# RS485.net
KiCad netlist of a schematic drawn in Altium Designer
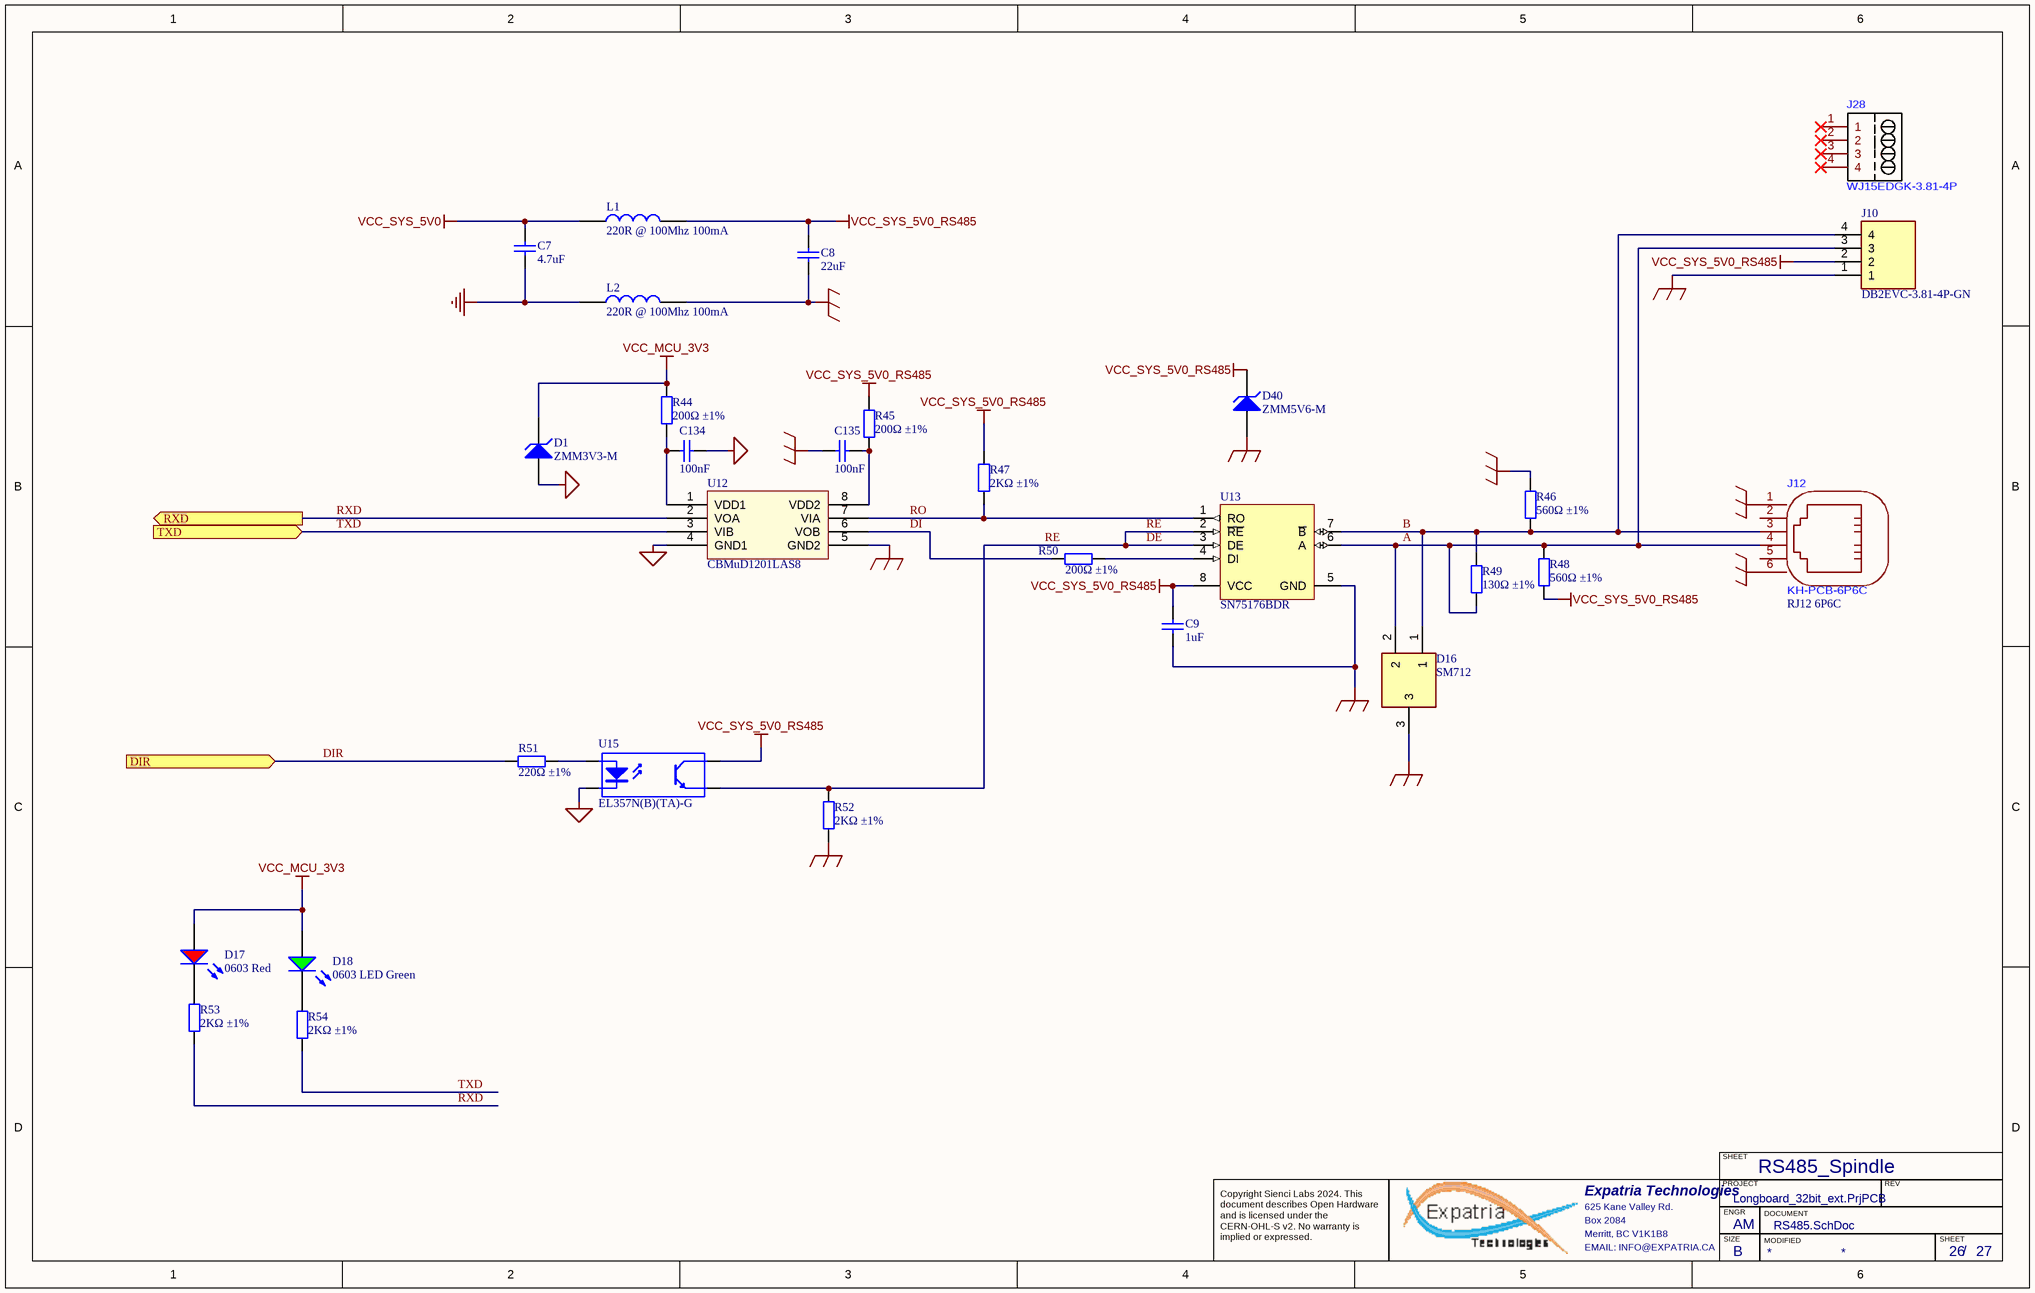
[diagram p0: RS485.SchDoc]

(export (version "E")
  (design (tool "Eeschema 10.0.6"))
  (components
    (comp (ref "C7")
      (value "4.7uF")
      (footprint "0805_C")
      (description "Chip capacitors")
      (fields
        (field (name "MANUFACTURER") "Samsung Electro-Mechanics")
        (field (name "MANUFACTURER PART NUMBER") "CL21A475KAQNNNE")
      )
      (libsource (lib "Cap") (part "0805 4.7uF (475) 10% 25V"))
    )
    (comp (ref "C8")
      (value "22uF")
      (footprint "0805_C")
      (description "25V 22uF X5R ±20% 0805 Multilayer Ceramic Capacitors MLCC - SMD/SMT ROHS")
      (fields (field (name "MANUFACTURER") "Samsung Electro-Mechanics") (field (name "TOLERANCE") "20%"))
      (libsource (lib "Sienci_Labs") (part "0805 22uF (226) 20% 25V"))
    )
    (comp (ref "C9")
      (value "1uF")
      (footprint "0603_C")
      (description "Chip capacitors")
      (fields
        (field (name "MANUFACTURER") "Samsung Electro-Mechanics")
        (field (name "MANUFACTURER PART NUMBER") "CL10A105KB8NNNC")
      )
      (libsource (lib "Cap") (part "0603 1uF (105) 10% 50V"))
    )
    (comp (ref "C134")
      (value "100nF")
      (footprint "0402_C")
      (description "16V 100nF X7R ±10% 0402 Multilayer Ceramic Capacitors MLCC - SMD/SMT ROHS")
      (fields (field (name "MANUFACTURER") "Samsung Electro-Mechanics") (field (name "TOLERANCE") "10%"))
      (libsource (lib "Sienci_Labs") (part "0402 100nF (104) 10% 16V"))
    )
    (comp (ref "C135")
      (value "100nF")
      (footprint "0402_C")
      (description "16V 100nF X7R ±10% 0402 Multilayer Ceramic Capacitors MLCC - SMD/SMT ROHS")
      (fields (field (name "MANUFACTURER") "Samsung Electro-Mechanics") (field (name "TOLERANCE") "10%"))
      (libsource (lib "Sienci_Labs") (part "0402 100nF (104) 10% 16V"))
    )
    (comp (ref "D1")
      (value "ZMM3V3-M")
      (footprint "LL-34")
      (description "Single 3.1V~3.5V 500mW 3.3V LL-34 Zener Diodes ROHS")
      (fields (field (name "MANUFACTURER") "ST(Semtech)"))
      (libsource (lib "Sienci_Labs") (part "LL-34 ZMM3V3-M"))
    )
    (comp (ref "D16")
      (value "SM712")
      (footprint "SOT95P230X117-3N")
      (description "Bidirectional 12V (Max), 7V (Max) 7.5V / 13.3V 10V / 20V 12A(8/20us) SOT-23-3 TVS RoHS")
      (fields (field (name "MANUFACTURER") "DOWO"))
      (libsource (lib "Sienci_Labs") (part "CDSOT23-SM712"))
    )
    (comp (ref "D17")
      (value "0603 Red")
      (footprint "0603_LED_S1")
      (description "-40℃~+85℃ Red 0603 Light Emitting Diodes (LED) ROHS")
      (fields
        (field (name "MANUFACTURER") "Hubei KENTO Elec")
        (field (name "MANUFACTURER PART NUMBER") "KT-0603R")
      )
      (libsource (lib "Sienci_Labs") (part "KT-0603R"))
    )
    (comp (ref "D18")
      (value "0603 LED Green")
      (footprint "0603_LED_S1 - GREEN")
      (description "20mA -40℃~+85℃ 515nm~530nm Emerald 120° 60mW 0603 Light Emitting Diodes (LED) ROHS")
      (fields (field (name "MANUFACTURER PART NUMBER") "MHT192UGCT") (field (name "MANUFACTURER") "MEIHUA"))
      (libsource (lib "Sienci_Labs") (part "MHT192UGCT"))
    )
    (comp (ref "D40")
      (value "ZMM5V6-M")
      (footprint "LL-34")
      (description "Single 500mW 5.2V~6V 5.6V LL-34 Zener Diodes ROHS")
      (fields (field (name "MANUFACTURER PART NUMBER") "ZMM5V6") (field (name "MANUFACTURER") "HXY MOSFET"))
      (libsource (lib "Sienci_Labs") (part "LL-34 ZMM5V6-M"))
    )
    (comp (ref "J10")
      (value "DB2EVC-3.81-4P-GN")
      (footprint "CONN-TH_5P-P3.81_DB2EVC-3.81-4p")
      (description "3.81mm Green Board Edge/Receptacle-Close Push-Pull,P=3.81mm Pluggable System Terminal Block ROHS")
      (fields (field (name "MANUFACTURER") "DIBO"))
      (libsource (lib "Sienci_Labs") (part "DB2EVC-3.81-4P-GN"))
    )
    (comp (ref "J12")
      (value "KH-PCB-6P6C")
      (footprint "RJ11-TH_DS1133-S60BPX")
      (fields
        (field (name "MANUFACTURER") "Shenzhen Kinghelm Elec")
        (field (name "ALTIUM_VALUE") "RJ12 6P6C")
      )
      (libsource (lib "Sienci_Labs") (part "KH-PCB-6P6C"))
    )
    (comp (ref "J28")
      (value "WJ15EDGK-3.81-4P")
      (description "3.81mm Green Plug P=3.81mm Pluggable System Terminal Block ROHS")
      (fields (field (name "MANUFACTURER") "Ningbo"))
      (libsource (lib "Sienci_Labs") (part "WJ15EDGK-3.81-4P"))
    )
    (comp (ref "L1")
      (value "220R @ 100Mhz 100mA")
      (footprint "0402_L")
      (description "700mΩ ±25% 220Ω@100MHz 0402 Ferrite Beads ROHS")
      (fields
        (field (name "MANUFACTURER PART NUMBER") "CBG100505U221T")
        (field (name "MANUFACTURER") "FH (Guangdong Fenghua Advanced Tech)")
      )
      (libsource (lib "Sienci_Labs") (part "0402 220R@100Mhz 0.1A"))
    )
    (comp (ref "L2")
      (value "220R @ 100Mhz 100mA")
      (footprint "0402_L")
      (description "700mΩ ±25% 220Ω@100MHz 0402 Ferrite Beads ROHS")
      (fields
        (field (name "MANUFACTURER PART NUMBER") "CBG100505U221T")
        (field (name "MANUFACTURER") "FH (Guangdong Fenghua Advanced Tech)")
      )
      (libsource (lib "Sienci_Labs") (part "0402 220R@100Mhz 0.1A"))
    )
    (comp (ref "R44")
      (value "200Ω ±1%")
      (footprint "0402_R")
      (description "Chip resistor")
      (fields
        (field (name "MANUFACTURER") "Uniroyal Elec")
        (field (name "MANUFACTURER PART NUMBER") "0402WGF2000TCE")
      )
      (libsource (lib "RES") (part "0402 200R (2000) 1%"))
    )
    (comp (ref "R45")
      (value "200Ω ±1%")
      (footprint "0402_R")
      (description "Chip resistor")
      (fields
        (field (name "MANUFACTURER") "Uniroyal Elec")
        (field (name "MANUFACTURER PART NUMBER") "0402WGF2000TCE")
      )
      (libsource (lib "RES") (part "0402 200R (2000) 1%"))
    )
    (comp (ref "R46")
      (value "560Ω ±1%")
      (footprint "0603_R")
      (description "Chip resistor")
      (fields
        (field (name "MANUFACTURER") "Uniroyal Elec")
        (field (name "MANUFACTURER PART NUMBER") "0603WAF5600T5E")
      )
      (libsource (lib "RES") (part "0603 560R (5600) 1%"))
    )
    (comp (ref "R47")
      (value "2KΩ ±1%")
      (footprint "0603_R")
      (description "Chip resistor")
      (fields
        (field (name "MANUFACTURER") "Uniroyal Elec")
        (field (name "MANUFACTURER PART NUMBER") "0603WAF2001T5E")
      )
      (libsource (lib "RES") (part "0603 2K (2001) 1%"))
    )
    (comp (ref "R48")
      (value "560Ω ±1%")
      (footprint "0603_R")
      (description "Chip resistor")
      (fields
        (field (name "MANUFACTURER") "Uniroyal Elec")
        (field (name "MANUFACTURER PART NUMBER") "0603WAF5600T5E")
      )
      (libsource (lib "RES") (part "0603 560R (5600) 1%"))
    )
    (comp (ref "R49")
      (value "130Ω ±1%")
      (footprint "0603_R")
      (description "Chip resistor")
      (fields
        (field (name "MANUFACTURER") "Uniroyal Elec")
        (field (name "MANUFACTURER PART NUMBER") "0603WAF1300T5E")
      )
      (libsource (lib "RES") (part "0603 130R (1300) 1%"))
    )
    (comp (ref "R50")
      (value "200Ω ±1%")
      (footprint "0402_R")
      (description "Chip resistor")
      (fields
        (field (name "MANUFACTURER") "Uniroyal Elec")
        (field (name "MANUFACTURER PART NUMBER") "0402WGF2000TCE")
      )
      (libsource (lib "") (part "0402 200R (2000) 1%_1"))
    )
    (comp (ref "R51")
      (value "220Ω ±1%")
      (footprint "0402_R")
      (description "Chip resistor")
      (fields
        (field (name "MANUFACTURER") "Uniroyal Elec")
        (field (name "MANUFACTURER PART NUMBER") "0402WGF2200TCE")
      )
      (libsource (lib "RES") (part "0402 220R (2200) 1%"))
    )
    (comp (ref "R52")
      (value "2KΩ ±1%")
      (footprint "0603_R")
      (description "Chip resistor")
      (fields
        (field (name "MANUFACTURER") "Uniroyal Elec")
        (field (name "MANUFACTURER PART NUMBER") "0603WAF2001T5E")
      )
      (libsource (lib "RES") (part "0603 2K (2001) 1%"))
    )
    (comp (ref "R53")
      (value "2KΩ ±1%")
      (footprint "0603_R")
      (description "Chip resistor")
      (fields
        (field (name "MANUFACTURER") "Uniroyal Elec")
        (field (name "MANUFACTURER PART NUMBER") "0603WAF2001T5E")
      )
      (libsource (lib "RES") (part "0603 2K (2001) 1%"))
    )
    (comp (ref "R54")
      (value "2KΩ ±1%")
      (footprint "0603_R")
      (description "Chip resistor")
      (fields
        (field (name "MANUFACTURER") "Uniroyal Elec")
        (field (name "MANUFACTURER PART NUMBER") "0603WAF2001T5E")
      )
      (libsource (lib "RES") (part "0603 2K (2001) 1%"))
    )
    (comp (ref "U12")
      (value "CBMuD1201LAS8")
      (footprint "SOIC-8_150mil")
      (description "Dual Channel Isolator")
      (fields (field (name "MANUFACTURER") "Corebai Microelectronics"))
      (libsource (lib "Sienci_Labs") (part "CBMuD1201LAS8"))
    )
    (comp (ref "U13")
      (value "SN75176BDR")
      (footprint "SOIC-8_150mil")
      (description "RS-485/RS-422")
      (fields (field (name "MANUFACTURER") "Texas Instruments"))
      (libsource (lib "IC") (part "SN75176BDR_[C7063]"))
    )
    (comp (ref "U15")
      (value "EL357N(B)(TA)-G")
      (footprint "Miscellaneous Devices LC:SOP-4_P2.54")
      (description "Optocoupler SOP-4, EL357N(B)(TA)-G, Everlight Electronics")
      (fields (field (name "MANUFACTURER") "Everlight"))
      (libsource (lib "Sienci_Labs") (part "EL357N(B)(TA)-G_[C6649]"))
    )
  )
  (nets
    (net (code "1") (name "/A") (class "Default")
      (node (ref "D16") (pin "2") (pinfunction "2_2") (pintype "passive"))
      (node (ref "J10") (pin "3") (pinfunction "3_3") (pintype "passive"))
      (node (ref "J12") (pin "4") (pinfunction "PGD_4") (pintype "passive"))
      (node (ref "R48") (pin "1") (pinfunction "1_1") (pintype "passive"))
      (node (ref "R49") (pin "1") (pinfunction "1_1") (pintype "passive"))
      (node (ref "U13") (pin "6") (pinfunction "A_6") (pintype "bidirectional"))
    )
    (net (code "2") (name "/B") (class "Default")
      (node (ref "D16") (pin "1") (pinfunction "1_1") (pintype "passive"))
      (node (ref "J10") (pin "4") (pinfunction "4_4") (pintype "passive"))
      (node (ref "J12") (pin "3") (pinfunction "VSS_3") (pintype "passive"))
      (node (ref "R46") (pin "2") (pinfunction "2_2") (pintype "passive"))
      (node (ref "R49") (pin "2") (pinfunction "2_2") (pintype "passive"))
      (node (ref "U13") (pin "7") (pinfunction "~{B}_7") (pintype "bidirectional"))
    )
    (net (code "3") (name "/DE") (class "Default")
      (node (ref "R52") (pin "2") (pinfunction "2_2") (pintype "passive"))
      (node (ref "U13") (pin "2") (pinfunction "~{RE}_2") (pintype "input"))
      (node (ref "U13") (pin "3") (pinfunction "DE_3") (pintype "input"))
      (node (ref "U15") (pin "3") (pinfunction "E_3") (pintype "passive"))
    )
    (net (code "4") (name "/DI") (class "Default")
      (node (ref "R50") (pin "2") (pinfunction "2_2") (pintype "passive"))
      (node (ref "U12") (pin "6") (pinfunction "VOB_6") (pintype "passive"))
    )
    (net (code "5") (name "/DIR") (class "Default")
      (node (ref "R51") (pin "2") (pinfunction "2_2") (pintype "passive"))
    )
    (net (code "6") (name "/RO") (class "Default")
      (node (ref "R47") (pin "1") (pinfunction "1_1") (pintype "passive"))
      (node (ref "U12") (pin "7") (pinfunction "VIA_7") (pintype "passive"))
      (node (ref "U13") (pin "1") (pinfunction "RO_1") (pintype "output"))
    )
    (net (code "7") (name "/RXD") (class "Default")
      (node (ref "R53") (pin "1") (pinfunction "1_1") (pintype "passive"))
      (node (ref "U12") (pin "2") (pinfunction "VOA_2") (pintype "passive"))
    )
    (net (code "8") (name "/TXD") (class "Default")
      (node (ref "R54") (pin "1") (pinfunction "1_1") (pintype "passive"))
      (node (ref "U12") (pin "3") (pinfunction "VIB_3") (pintype "passive"))
    )
    (net (code "9") (name "GND") (class "Default")
      (node (ref "C7") (pin "1") (pinfunction "1_1") (pintype "passive"))
      (node (ref "L2") (pin "1") (pinfunction "1_1") (pintype "passive"))
    )
    (net (code "10") (name "MCU_GND") (class "Default")
      (node (ref "C134") (pin "2") (pinfunction "2_2") (pintype "passive"))
      (node (ref "D1") (pin "1") (pinfunction "A_1") (pintype "passive"))
      (node (ref "U12") (pin "4") (pinfunction "GND1_4") (pintype "passive"))
      (node (ref "U15") (pin "2") (pinfunction "K_2") (pintype "passive"))
    )
    (net (code "11") (name "MOD_GND") (class "Default")
      (node (ref "C135") (pin "1") (pinfunction "1_1") (pintype "passive"))
      (node (ref "C8") (pin "1") (pinfunction "1_1") (pintype "passive"))
      (node (ref "C9") (pin "1") (pinfunction "1_1") (pintype "passive"))
      (node (ref "D16") (pin "3") (pinfunction "3_3") (pintype "passive"))
      (node (ref "D40") (pin "1") (pinfunction "A_1") (pintype "passive"))
      (node (ref "J10") (pin "1") (pinfunction "1_1") (pintype "passive"))
      (node (ref "J12") (pin "1") (pinfunction "MCLR_1") (pintype "passive"))
      (node (ref "J12") (pin "6") (pinfunction "NC_6") (pintype "passive"))
      (node (ref "L2") (pin "2") (pinfunction "2_2") (pintype "passive"))
      (node (ref "R46") (pin "1") (pinfunction "1_1") (pintype "passive"))
      (node (ref "R52") (pin "1") (pinfunction "1_1") (pintype "passive"))
      (node (ref "U12") (pin "5") (pinfunction "GND2_5") (pintype "passive"))
      (node (ref "U13") (pin "5") (pinfunction "GND_5") (pintype "power_in"))
    )
    (net (code "12") (name "Net-(D17-PadK)") (class "Default")
      (node (ref "D17") (pin "K") (pinfunction "K_K") (pintype "passive"))
      (node (ref "R53") (pin "2") (pinfunction "2_2") (pintype "passive"))
    )
    (net (code "13") (name "Net-(D18-PadK)") (class "Default")
      (node (ref "D18") (pin "K") (pinfunction "K_K") (pintype "passive"))
      (node (ref "R54") (pin "2") (pinfunction "2_2") (pintype "passive"))
    )
    (net (code "14") (name "Net-(U12-VDD1)") (class "Default")
      (node (ref "C134") (pin "1") (pinfunction "1_1") (pintype "passive"))
      (node (ref "R44") (pin "1") (pinfunction "1_1") (pintype "passive"))
      (node (ref "U12") (pin "1") (pinfunction "VDD1_1") (pintype "passive"))
    )
    (net (code "15") (name "Net-(U12-VDD2)") (class "Default")
      (node (ref "C135") (pin "2") (pinfunction "2_2") (pintype "passive"))
      (node (ref "R45") (pin "1") (pinfunction "1_1") (pintype "passive"))
      (node (ref "U12") (pin "8") (pinfunction "VDD2_8") (pintype "passive"))
    )
    (net (code "16") (name "Net-(U13-DI)") (class "Default")
      (node (ref "R50") (pin "1") (pinfunction "1_1") (pintype "passive"))
      (node (ref "U13") (pin "4") (pinfunction "DI_4") (pintype "input"))
    )
    (net (code "17") (name "Net-(U15-A)") (class "Default")
      (node (ref "R51") (pin "1") (pinfunction "1_1") (pintype "passive"))
      (node (ref "U15") (pin "1") (pinfunction "A_1") (pintype "passive"))
    )
    (net (code "18") (name "VCC_MCU_3V3") (class "Default")
      (node (ref "D1") (pin "2") (pinfunction "K_2") (pintype "passive"))
      (node (ref "D17") (pin "A") (pinfunction "A_A") (pintype "passive"))
      (node (ref "D18") (pin "A") (pinfunction "A_A") (pintype "passive"))
      (node (ref "R44") (pin "2") (pinfunction "2_2") (pintype "passive"))
    )
    (net (code "19") (name "VCC_SYS_5V0") (class "Default")
      (node (ref "C7") (pin "2") (pinfunction "2_2") (pintype "passive"))
      (node (ref "L1") (pin "1") (pinfunction "1_1") (pintype "passive"))
    )
    (net (code "20") (name "VCC_SYS_5V0_RS485") (class "Default")
      (node (ref "C8") (pin "2") (pinfunction "2_2") (pintype "passive"))
      (node (ref "C9") (pin "2") (pinfunction "2_2") (pintype "passive"))
      (node (ref "D40") (pin "2") (pinfunction "K_2") (pintype "passive"))
      (node (ref "J10") (pin "2") (pinfunction "2_2") (pintype "passive"))
      (node (ref "L1") (pin "2") (pinfunction "2_2") (pintype "passive"))
      (node (ref "R45") (pin "2") (pinfunction "2_2") (pintype "passive"))
      (node (ref "R47") (pin "2") (pinfunction "2_2") (pintype "passive"))
      (node (ref "R48") (pin "2") (pinfunction "2_2") (pintype "passive"))
      (node (ref "U13") (pin "8") (pinfunction "VCC_8") (pintype "power_in"))
      (node (ref "U15") (pin "4") (pinfunction "C_4") (pintype "passive"))
    )
    (net (code "21") (name "unconnected-(J12-PGC-Pad5)") (class "Default")
      (node (ref "J12") (pin "5") (pinfunction "PGC_5") (pintype "passive"))
    )
    (net (code "22") (name "unconnected-(J12-VDD-Pad2)") (class "Default")
      (node (ref "J12") (pin "2") (pinfunction "VDD_2") (pintype "passive"))
    )
    (net (code "23") (name "unconnected-(J28-Pad1)") (class "Default")
      (node (ref "J28") (pin "1") (pinfunction "1_1") (pintype "passive+no_connect"))
    )
    (net (code "24") (name "unconnected-(J28-Pad2)") (class "Default")
      (node (ref "J28") (pin "2") (pinfunction "2_2") (pintype "passive+no_connect"))
    )
    (net (code "25") (name "unconnected-(J28-Pad3)") (class "Default")
      (node (ref "J28") (pin "3") (pinfunction "3_3") (pintype "passive+no_connect"))
    )
    (net (code "26") (name "unconnected-(J28-Pad4)") (class "Default")
      (node (ref "J28") (pin "4") (pinfunction "4_4") (pintype "passive+no_connect"))
    )
  )
)
